# IMU-SD_Card-CAN-CH340.net
KiCad netlist of a schematic drawn in Altium Designer
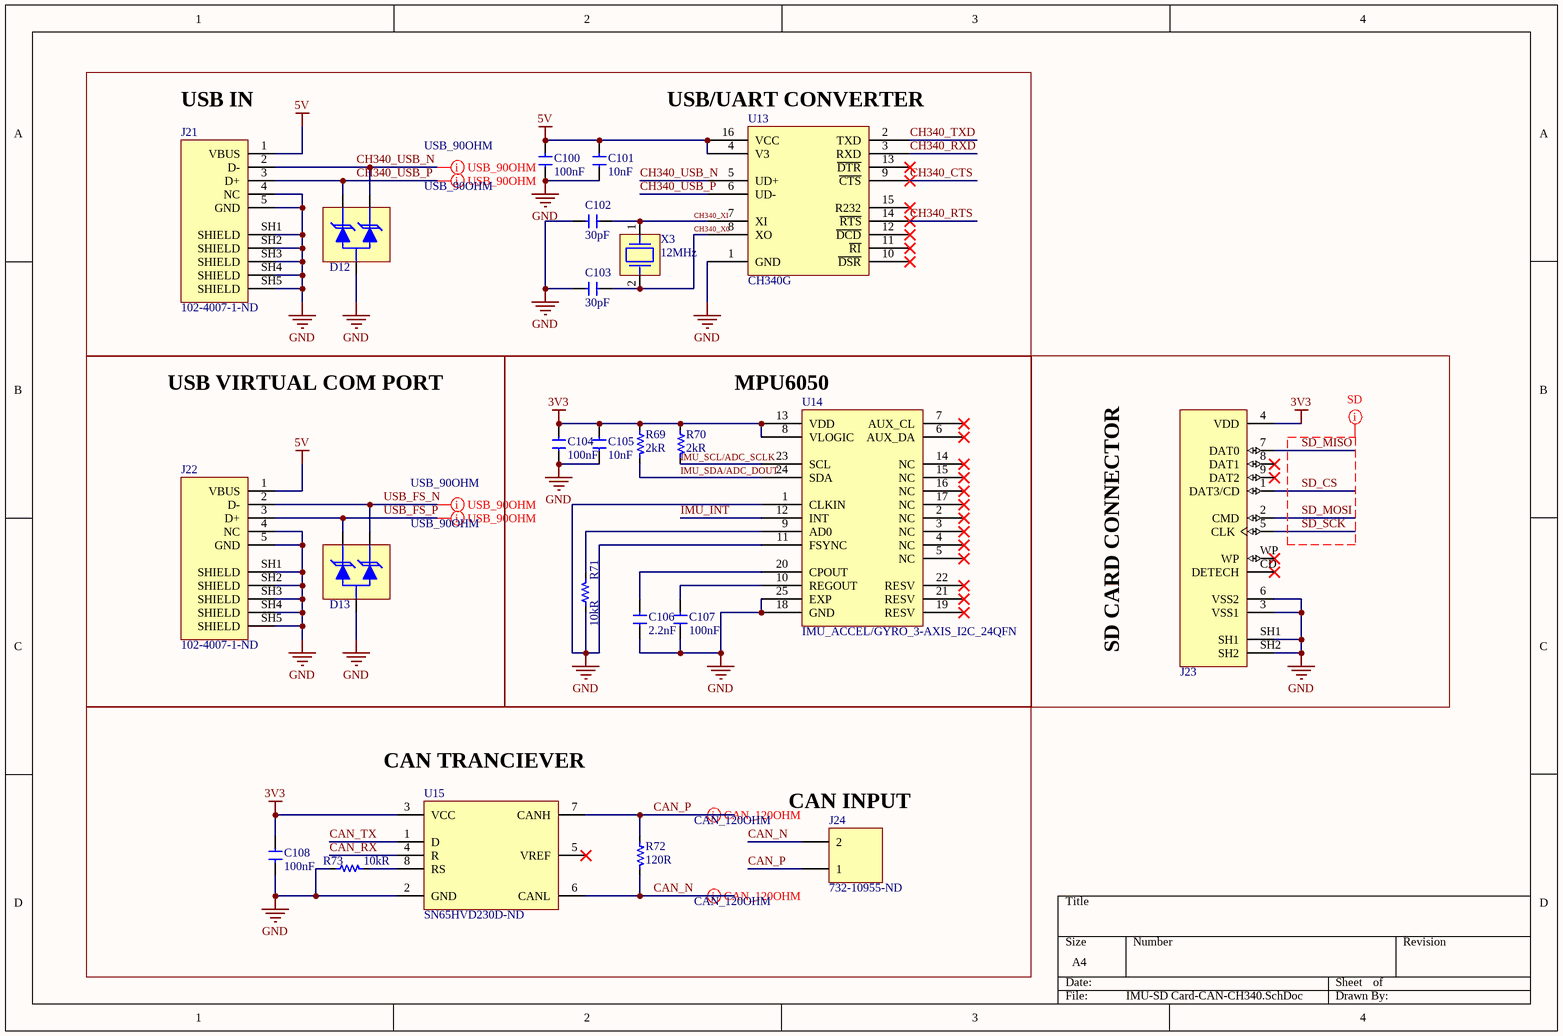
[diagram p0: IMU-SD Card-CAN-CH340.SchDoc]

(export (version "E")
  (design (tool "Eeschema 10.0.6"))
  (components
    (comp (ref "C100")
      (value "CAP_0.1uF_%20_50V_0805_X7R_CER")
      (footprint "0805_CAP")
      (description "Cap Ceramic 0.1uF 50V X7R 20% SMD 0805 125C Paper T/R")
      (fields
        (field (name "MANUFACTURER") "KEMET")
        (field (name "MANUFACTURER PART NUMBER") "C0805C104M5RACTU")
        (field (name "CAPACITANCE") "100nF")
      )
      (libsource (lib "Main Component Library") (part "CAP_0.1uF_%20_50V_0805_X7R_CER"))
    )
    (comp (ref "C101")
      (value "CAP_10nF_%10_50V_0805_X7R_CER")
      (footprint "0805_CAP")
      (description "CAP CER 10000PF 50V X7R 0805")
      (fields
        (field (name "MANUFACTURER") "Samsung")
        (field (name "MANUFACTURER PART NUMBER") "CL21B103KBANNNC")
        (field (name "CAPACITANCE") "10nF")
      )
      (libsource (lib "Main Component Library") (part "CAP_10nF_%10_50V_0805_X7R_CER"))
    )
    (comp (ref "C102")
      (value "CAP_30pF_%5_50V_0805_C0G/NP0_CER")
      (footprint "0805_CAP")
      (description "0805 30 pF 50 V ±5% Tolerance C0G/NP0 Surface Mount Multilayer Ceramic Capacitor")
      (fields
        (field (name "MANUFACTURER") "Kyocera AVX")
        (field (name "MANUFACTURER PART NUMBER") "08055A300JAT2A")
        (field (name "CAPACITANCE") "30pF")
      )
      (libsource (lib "Main Component Library") (part "CAP_30pF_%5_50V_0805_C0G/NP0_CER"))
    )
    (comp (ref "C103")
      (value "CAP_30pF_%5_50V_0805_C0G/NP0_CER")
      (footprint "0805_CAP")
      (description "0805 30 pF 50 V ±5% Tolerance C0G/NP0 Surface Mount Multilayer Ceramic Capacitor")
      (fields
        (field (name "MANUFACTURER") "Kyocera AVX")
        (field (name "MANUFACTURER PART NUMBER") "08055A300JAT2A")
        (field (name "CAPACITANCE") "30pF")
      )
      (libsource (lib "Main Component Library") (part "CAP_30pF_%5_50V_0805_C0G/NP0_CER"))
    )
    (comp (ref "C104")
      (value "CAP_0.1uF_%20_50V_0805_X7R_CER")
      (footprint "0805_CAP")
      (description "Cap Ceramic 0.1uF 50V X7R 20% SMD 0805 125C Paper T/R")
      (fields
        (field (name "MANUFACTURER") "KEMET")
        (field (name "MANUFACTURER PART NUMBER") "C0805C104M5RACTU")
        (field (name "CAPACITANCE") "100nF")
      )
      (libsource (lib "Main Schematic Library") (part "CAP_0.1uF_%20_50V_0805_X7R_CER"))
    )
    (comp (ref "C105")
      (value "CAP_10nF_%10_50V_0805_X7R_CER")
      (footprint "0805_CAP")
      (description "CAP CER 10000PF 50V X7R 0805")
      (fields
        (field (name "MANUFACTURER") "Samsung")
        (field (name "MANUFACTURER PART NUMBER") "CL21B103KBANNNC")
        (field (name "CAPACITANCE") "10nF")
      )
      (libsource (lib "Main Schematic Library") (part "CAP_10nF_%10_50V_0805_X7R_CER"))
    )
    (comp (ref "C106")
      (value "CAP_2200pF_%10_50V_0805_X7R_CER")
      (footprint "0805_CAP")
      (description "贴片陶瓷电容  2.2nF ±10% 50V X7R 0805")
      (fields
        (field (name "MANUFACTURER") "Samsung")
        (field (name "MANUFACTURER PART NUMBER") "CL21B222KBANNNC")
        (field (name "CAPACITANCE") "2.2nF")
      )
      (libsource (lib "Main Schematic Library") (part "CAP_2200pF_%10_50V_0805_X7R_CER"))
    )
    (comp (ref "C107")
      (value "CAP_0.1uF_%20_50V_0805_X7R_CER")
      (footprint "0805_CAP")
      (description "Cap Ceramic 0.1uF 50V X7R 20% SMD 0805 125C Paper T/R")
      (fields
        (field (name "MANUFACTURER") "KEMET")
        (field (name "MANUFACTURER PART NUMBER") "C0805C104M5RACTU")
        (field (name "CAPACITANCE") "100nF")
      )
      (libsource (lib "Main Schematic Library") (part "CAP_0.1uF_%20_50V_0805_X7R_CER"))
    )
    (comp (ref "C108")
      (value "CAP_0.1uF_%20_50V_0805_X7R_CER")
      (footprint "0805_CAP")
      (description "Cap Ceramic 0.1uF 50V X7R 20% SMD 0805 125C Paper T/R")
      (fields
        (field (name "MANUFACTURER") "KEMET")
        (field (name "MANUFACTURER PART NUMBER") "C0805C104M5RACTU")
        (field (name "CAPACITANCE") "100nF")
      )
      (libsource (lib "Main Schematic Library") (part "CAP_0.1uF_%20_50V_0805_X7R_CER"))
    )
    (comp (ref "D12")
      (value "DIODE_TVS_3.3VWM_8VC_SOT23")
      (footprint "SOT170P237X110-3N")
      (description "ESD Suppressor TVS Uni-Dir 3.3V 3-Pin SOT-23 T/R")
      (fields (field (name "MANUFACTURER") "MCC") (field (name "MANUFACTURER PART NUMBER") "ESD3V3AP-TP"))
      (libsource (lib "Main Schematic Library") (part "DIODE_TVS_3.3VWM_8VC_SOT23"))
    )
    (comp (ref "D13")
      (value "DIODE_TVS_3.3VWM_8VC_SOT23")
      (footprint "SOT170P237X110-3N")
      (description "ESD Suppressor TVS Uni-Dir 3.3V 3-Pin SOT-23 T/R")
      (fields (field (name "MANUFACTURER") "MCC") (field (name "MANUFACTURER PART NUMBER") "ESD3V3AP-TP"))
      (libsource (lib "Main Schematic Library") (part "DIODE_TVS_3.3VWM_8VC_SOT23"))
    )
    (comp (ref "J21")
      (value "Micro USB2.0")
      (footprint "MICRO_USB2.0_CUI_UJ2-MIBH2-4-SMT")
      (description "Conn Micro USB 2.0 Type B F 5 POS 0.65mm Solder RA SMD 5 Terminal 1 Port T/R")
      (fields
        (field (name "MANUFACTURER") "CUI Devices")
        (field (name "MANUFACTURER PART NUMBER") "UJ2-MIBH2-4-SMT-TR")
        (field (name "SUPPLIER PART NUMBER 1") "102-4007-1-ND")
      )
      (libsource (lib "Main Schematic Library") (part "CONN_RCPT_USB2.0_MICRO B_SMD_R/A"))
    )
    (comp (ref "J22")
      (value "Micro USB2.0")
      (footprint "MICRO_USB2.0_CUI_UJ2-MIBH2-4-SMT")
      (description "Conn Micro USB 2.0 Type B F 5 POS 0.65mm Solder RA SMD 5 Terminal 1 Port T/R")
      (fields
        (field (name "MANUFACTURER") "CUI Devices")
        (field (name "MANUFACTURER PART NUMBER") "UJ2-MIBH2-4-SMT-TR")
        (field (name "SUPPLIER PART NUMBER 1") "102-4007-1-ND")
      )
      (libsource (lib "Main Schematic Library") (part "CONN_RCPT_USB2.0_MICRO B_SMD_R/A"))
    )
    (comp (ref "J23")
      (value "CONN_SD CARD_L-KLS1-SD-001")
      (footprint "SD CARD L-KLS1-TF-003")
      (description "Conn; IC Socket; SD Memory Card; Push/Push; SD Ser.")
      (fields
        (field (name "MF") "{'manufacturer': u'Amphenol ICC (Commercial Products)'}")
        (field (name "MP") "101003136802")
      )
      (libsource (lib "Main Schematic Library") (part "CONN_SD CARD_L-KLS1-SD-001"))
    )
    (comp (ref "J24")
      (value "CONN_1X2_Terminal Block")
      (footprint "1x2_TERMINAL BLOCK")
      (description "Series 1377 - 5.00 mm Horizontal Entry with Pressure Clamp WR-TBL, 2 pin")
      (fields
        (field (name "MANUFACTURER") "Wurth Electronics")
        (field (name "MANUFACTURER PART NUMBER") "691137710002")
        (field (name "SUPPLIER PART NUMBER 1") "732-10955-ND")
      )
      (libsource (lib "Main Schematic Library") (part "CONN_1X2_Terminal Block"))
    )
    (comp (ref "R69")
      (value "RES_2K OHM_1%_0805_1/8W_SMD")
      (footprint "0805_RES")
      (description "Res Thick Film 0805 2K Ohm 1% 0.125W(1/8W) ±100ppm/C Pad SMD Automotive T/R")
      (fields
        (field (name "MANUFACTURER") "Yageo")
        (field (name "MANUFACTURER PART NUMBER") "AC0805FR-072KL")
        (field (name "RESISTANCE") "2kR")
      )
      (libsource (lib "Main Component Library") (part "RES_2K OHM_1%_0805_1/8W_SMD"))
    )
    (comp (ref "R70")
      (value "RES_2K OHM_1%_0805_1/8W_SMD")
      (footprint "0805_RES")
      (description "Res Thick Film 0805 2K Ohm 1% 0.125W(1/8W) ±100ppm/C Pad SMD Automotive T/R")
      (fields
        (field (name "MANUFACTURER") "Yageo")
        (field (name "MANUFACTURER PART NUMBER") "AC0805FR-072KL")
        (field (name "RESISTANCE") "2kR")
      )
      (libsource (lib "Main Component Library") (part "RES_2K OHM_1%_0805_1/8W_SMD"))
    )
    (comp (ref "R71")
      (value "10k Ohms")
      (footprint "0805_RES")
      (description "Res SMD 0805 10K 1% 0.125W T.C.100PPM")
      (fields
        (field (name "MANUFACTURER") "TDK")
        (field (name "MANUFACTURER PART NUMBER") "C2012X7R1H104K085AA")
        (field (name "RESISTANCE") "10kR")
      )
      (libsource (lib "Main Schematic Library") (part "RES_10K OHM_%1_0805_1/8W"))
    )
    (comp (ref "R72")
      (value "120R")
      (footprint "0805_RES")
      (description "Res Thick Film 0805 120 Ohm 1% 0.125W(1/8W) ±100ppm/C Pad SMD T/R")
      (fields
        (field (name "MANUFACTURER") "Vishay")
        (field (name "MANUFACTURER PART NUMBER") "CRCW0805120RFKEAC")
      )
      (libsource (lib "Main Schematic Library") (part "RES_120 OHM_1%_0805_1/8W"))
    )
    (comp (ref "R73")
      (value "10k Ohms")
      (footprint "0805_RES")
      (description "Res SMD 0805 10K 1% 0.125W T.C.100PPM")
      (fields
        (field (name "MANUFACTURER") "TDK")
        (field (name "MANUFACTURER PART NUMBER") "C2012X7R1H104K085AA")
        (field (name "RESISTANCE") "10kR")
      )
      (libsource (lib "Main Schematic Library") (part "RES_10K OHM_%1_0805_1/8W"))
    )
    (comp (ref "U13")
      (value "CH340G")
      (footprint "SOIC127P600X180-16N")
      (description "USB to UART Converter IC")
      (fields (field (name "MANUFACTURER") "WCH"))
      (libsource (lib "Main Schematic Library") (part "IC_USB/UART_CH340G"))
    )
    (comp (ref "U14")
      (value "IMU_ACCEL/GYRO_3-AXIS_I2C_24QFN")
      (footprint "IC_MPU6050")
      (description "IMU ACCEL/GYRO 3-AXIS I2C 24QFN")
      (fields
        (field (name "MANUFACTURER") "TDK InvenSense")
        (field (name "MANUFACTURER PART NUMBER") "MPU-6050")
      )
      (libsource (lib "Main Schematic Library") (part "IMU_ACCEL/GYRO_3-AXIS_I2C_24QFN"))
    )
    (comp (ref "U15")
      (value "IC_TRANSCEIVER CAN_SN65HVD230D")
      (footprint "SOIC127P599X175-8N")
      (description "SN65HVD230 3.3 V Can Transceiver")
      (fields
        (field (name "MANUFACTURER") "Texas Instruments")
        (field (name "MANUFACTURER PART NUMBER") "SN65HVD230D")
        (field (name "SUPPLIER PART NUMBER 1") "SN65HVD230D-ND")
      )
      (libsource (lib "Main Schematic Library") (part "IC_TRANSCEIVER CAN_SN65HVD230D"))
    )
    (comp (ref "X3")
      (value "CRYSTAL_12MHz_20PF_SMD")
      (footprint "HC-49/US")
      (description "Crystal 12MHz ±25ppm (Tol) ±35ppm (Stability) 20pF FUND 50Ohm 2-Pin HC-49/US SMD T/R")
      (fields
        (field (name "MANUFACTURER") "Abracon")
        (field (name "MANUFACTURER PART NUMBER") "ABLS-12.000MHZ-20-B-3-H-T")
        (field (name "FREQUENCY") "12MHz")
      )
      (libsource (lib "Main Schematic Library") (part "CRYSTAL_12MHz_20PF_SMD"))
    )
  )
  (nets
    (net (code "1") (name "/CAN_N") (class "Default")
      (node (ref "J24") (pin "2") (pinfunction "2_2") (pintype "passive"))
      (node (ref "R72") (pin "1") (pinfunction "1_1") (pintype "passive"))
      (node (ref "U15") (pin "6") (pinfunction "CANL_6") (pintype "passive"))
    )
    (net (code "2") (name "/CAN_P") (class "Default")
      (node (ref "J24") (pin "1") (pinfunction "1_1") (pintype "passive"))
      (node (ref "R72") (pin "2") (pinfunction "2_2") (pintype "passive"))
      (node (ref "U15") (pin "7") (pinfunction "CANH_7") (pintype "passive"))
    )
    (net (code "3") (name "/CAN_RX") (class "Default")
      (node (ref "U15") (pin "4") (pinfunction "R_4") (pintype "passive"))
    )
    (net (code "4") (name "/CAN_TX") (class "Default")
      (node (ref "U15") (pin "1") (pinfunction "D_1") (pintype "passive"))
    )
    (net (code "5") (name "/CH340_CTS") (class "Default")
      (node (ref "U13") (pin "9") (pinfunction "~{CTS}_9") (pintype "passive+no_connect"))
    )
    (net (code "6") (name "/CH340_RTS") (class "Default")
      (node (ref "U13") (pin "14") (pinfunction "~{RTS}_14") (pintype "passive+no_connect"))
    )
    (net (code "7") (name "/CH340_RXD") (class "Default")
      (node (ref "U13") (pin "3") (pinfunction "RXD_3") (pintype "passive"))
    )
    (net (code "8") (name "/CH340_TXD") (class "Default")
      (node (ref "U13") (pin "2") (pinfunction "TXD_2") (pintype "passive"))
    )
    (net (code "9") (name "/CH340_USB_N") (class "Default")
      (node (ref "D12") (pin "1") (pinfunction "CATHODE_1_1") (pintype "passive"))
      (node (ref "J21") (pin "2") (pinfunction "D-_2") (pintype "passive"))
      (node (ref "U13") (pin "5") (pinfunction "UD+_5") (pintype "passive"))
    )
    (net (code "10") (name "/CH340_USB_P") (class "Default")
      (node (ref "D12") (pin "2") (pinfunction "CATHODE_2_2") (pintype "passive"))
      (node (ref "J21") (pin "3") (pinfunction "D+_3") (pintype "passive"))
      (node (ref "U13") (pin "6") (pinfunction "UD-_6") (pintype "passive"))
    )
    (net (code "11") (name "/CH340_X0") (class "Default")
      (node (ref "C103") (pin "2") (pinfunction "2_2") (pintype "passive"))
      (node (ref "U13") (pin "8") (pinfunction "XO_8") (pintype "passive"))
      (node (ref "X3") (pin "2") (pinfunction "2_2") (pintype "passive"))
    )
    (net (code "12") (name "/CH340_XI") (class "Default")
      (node (ref "C102") (pin "2") (pinfunction "2_2") (pintype "passive"))
      (node (ref "U13") (pin "7") (pinfunction "XI_7") (pintype "passive"))
      (node (ref "X3") (pin "1") (pinfunction "1_1") (pintype "passive"))
    )
    (net (code "13") (name "/IMU_INT") (class "Default")
      (node (ref "U14") (pin "12") (pinfunction "INT_12") (pintype "passive"))
    )
    (net (code "14") (name "/IMU_SCL{slash}ADC_SCLK") (class "Default")
      (node (ref "R70") (pin "1") (pinfunction "1_1") (pintype "passive"))
      (node (ref "U14") (pin "23") (pinfunction "SCL_23") (pintype "passive"))
    )
    (net (code "15") (name "/IMU_SDA{slash}ADC_DOUT") (class "Default")
      (node (ref "R69") (pin "1") (pinfunction "1_1") (pintype "passive"))
      (node (ref "U14") (pin "24") (pinfunction "SDA_24") (pintype "passive"))
    )
    (net (code "16") (name "/SD_CS") (class "Default")
      (node (ref "J23") (pin "1") (pinfunction "DAT3/CD_1") (pintype "bidirectional"))
    )
    (net (code "17") (name "/SD_MISO") (class "Default")
      (node (ref "J23") (pin "7") (pinfunction "DAT0_7") (pintype "bidirectional"))
    )
    (net (code "18") (name "/SD_MOSI") (class "Default")
      (node (ref "J23") (pin "2") (pinfunction "CMD_2") (pintype "bidirectional"))
    )
    (net (code "19") (name "/SD_SCK") (class "Default")
      (node (ref "J23") (pin "5") (pinfunction "CLK_5") (pintype "bidirectional"))
    )
    (net (code "20") (name "/USB_FS_N") (class "Default")
      (node (ref "D13") (pin "1") (pinfunction "CATHODE_1_1") (pintype "passive"))
      (node (ref "J22") (pin "2") (pinfunction "D-_2") (pintype "passive"))
    )
    (net (code "21") (name "/USB_FS_P") (class "Default")
      (node (ref "D13") (pin "2") (pinfunction "CATHODE_2_2") (pintype "passive"))
      (node (ref "J22") (pin "3") (pinfunction "D+_3") (pintype "passive"))
    )
    (net (code "22") (name "3V3") (class "Default")
      (node (ref "C104") (pin "2") (pinfunction "2_2") (pintype "passive"))
      (node (ref "C105") (pin "2") (pinfunction "2_2") (pintype "passive"))
      (node (ref "C108") (pin "2") (pinfunction "2_2") (pintype "passive"))
      (node (ref "J23") (pin "4") (pinfunction "VDD_4") (pintype "power_in"))
      (node (ref "R69") (pin "2") (pinfunction "2_2") (pintype "passive"))
      (node (ref "R70") (pin "2") (pinfunction "2_2") (pintype "passive"))
      (node (ref "U14") (pin "13") (pinfunction "VDD_13") (pintype "passive"))
      (node (ref "U14") (pin "8") (pinfunction "VLOGIC_8") (pintype "passive"))
      (node (ref "U15") (pin "3") (pinfunction "VCC_3") (pintype "passive"))
    )
    (net (code "23") (name "5V") (class "Default")
      (node (ref "C100") (pin "2") (pinfunction "2_2") (pintype "passive"))
      (node (ref "C101") (pin "2") (pinfunction "2_2") (pintype "passive"))
      (node (ref "J21") (pin "1") (pinfunction "VBUS_1") (pintype "passive"))
      (node (ref "J22") (pin "1") (pinfunction "VBUS_1") (pintype "passive"))
      (node (ref "U13") (pin "16") (pinfunction "VCC_16") (pintype "passive"))
      (node (ref "U13") (pin "4") (pinfunction "V3_4") (pintype "passive"))
    )
    (net (code "24") (name "GND") (class "Default")
      (node (ref "C100") (pin "1") (pinfunction "1_1") (pintype "passive"))
      (node (ref "C101") (pin "1") (pinfunction "1_1") (pintype "passive"))
      (node (ref "C102") (pin "1") (pinfunction "1_1") (pintype "passive"))
      (node (ref "C103") (pin "1") (pinfunction "1_1") (pintype "passive"))
      (node (ref "C104") (pin "1") (pinfunction "1_1") (pintype "passive"))
      (node (ref "C105") (pin "1") (pinfunction "1_1") (pintype "passive"))
      (node (ref "C106") (pin "1") (pinfunction "1_1") (pintype "passive"))
      (node (ref "C107") (pin "1") (pinfunction "1_1") (pintype "passive"))
      (node (ref "C108") (pin "1") (pinfunction "1_1") (pintype "passive"))
      (node (ref "D12") (pin "3") (pinfunction "ANODE_3") (pintype "passive"))
      (node (ref "D13") (pin "3") (pinfunction "ANODE_3") (pintype "passive"))
      (node (ref "J21") (pin "4") (pinfunction "NC_4") (pintype "passive"))
      (node (ref "J21") (pin "5") (pinfunction "GND_5") (pintype "passive"))
      (node (ref "J21") (pin "SH1") (pinfunction "SHIELD_SH1") (pintype "passive"))
      (node (ref "J21") (pin "SH2") (pinfunction "SHIELD_SH2") (pintype "passive"))
      (node (ref "J21") (pin "SH3") (pinfunction "SHIELD_SH3") (pintype "passive"))
      (node (ref "J21") (pin "SH4") (pinfunction "SHIELD_SH4") (pintype "passive"))
      (node (ref "J21") (pin "SH5") (pinfunction "SHIELD_SH5") (pintype "passive"))
      (node (ref "J22") (pin "4") (pinfunction "NC_4") (pintype "passive"))
      (node (ref "J22") (pin "5") (pinfunction "GND_5") (pintype "passive"))
      (node (ref "J22") (pin "SH1") (pinfunction "SHIELD_SH1") (pintype "passive"))
      (node (ref "J22") (pin "SH2") (pinfunction "SHIELD_SH2") (pintype "passive"))
      (node (ref "J22") (pin "SH3") (pinfunction "SHIELD_SH3") (pintype "passive"))
      (node (ref "J22") (pin "SH4") (pinfunction "SHIELD_SH4") (pintype "passive"))
      (node (ref "J22") (pin "SH5") (pinfunction "SHIELD_SH5") (pintype "passive"))
      (node (ref "J23") (pin "3") (pinfunction "VSS1_3") (pintype "power_in"))
      (node (ref "J23") (pin "6") (pinfunction "VSS2_6") (pintype "passive"))
      (node (ref "J23") (pin "SH1") (pinfunction "SH1_SH1") (pintype "passive"))
      (node (ref "J23") (pin "SH2") (pinfunction "SH2_SH2") (pintype "passive"))
      (node (ref "R71") (pin "2") (pinfunction "2_2") (pintype "passive"))
      (node (ref "R73") (pin "2") (pinfunction "2_2") (pintype "passive"))
      (node (ref "U13") (pin "1") (pinfunction "GND_1") (pintype "passive"))
      (node (ref "U14") (pin "1") (pinfunction "CLKIN_1") (pintype "passive"))
      (node (ref "U14") (pin "11") (pinfunction "FSYNC_11") (pintype "passive"))
      (node (ref "U14") (pin "18") (pinfunction "GND_18") (pintype "passive"))
      (node (ref "U14") (pin "25") (pinfunction "EXP_25") (pintype "power_in"))
      (node (ref "U15") (pin "2") (pinfunction "GND_2") (pintype "passive"))
    )
    (net (code "25") (name "Net-(U14-AD0)") (class "Default")
      (node (ref "R71") (pin "1") (pinfunction "1_1") (pintype "passive"))
      (node (ref "U14") (pin "9") (pinfunction "AD0_9") (pintype "passive"))
    )
    (net (code "26") (name "Net-(U14-CPOUT)") (class "Default")
      (node (ref "C106") (pin "2") (pinfunction "2_2") (pintype "passive"))
      (node (ref "U14") (pin "20") (pinfunction "CPOUT_20") (pintype "passive"))
    )
    (net (code "27") (name "Net-(U14-REGOUT)") (class "Default")
      (node (ref "C107") (pin "2") (pinfunction "2_2") (pintype "passive"))
      (node (ref "U14") (pin "10") (pinfunction "REGOUT_10") (pintype "passive"))
    )
    (net (code "28") (name "Net-(U15-RS)") (class "Default")
      (node (ref "R73") (pin "1") (pinfunction "1_1") (pintype "passive"))
      (node (ref "U15") (pin "8") (pinfunction "RS_8") (pintype "passive"))
    )
    (net (code "29") (name "unconnected-(J23-DAT1-Pad8)") (class "Default")
      (node (ref "J23") (pin "8") (pinfunction "DAT1_8") (pintype "bidirectional+no_connect"))
    )
    (net (code "30") (name "unconnected-(J23-DAT2-Pad9)") (class "Default")
      (node (ref "J23") (pin "9") (pinfunction "DAT2_9") (pintype "bidirectional+no_connect"))
    )
    (net (code "31") (name "unconnected-(J23-DETECH-PadCD)") (class "Default")
      (node (ref "J23") (pin "CD") (pinfunction "DETECH_CD") (pintype "passive+no_connect"))
    )
    (net (code "32") (name "unconnected-(J23-PadWP)") (class "Default")
      (node (ref "J23") (pin "WP") (pinfunction "WP_WP") (pintype "bidirectional+no_connect"))
    )
    (net (code "33") (name "unconnected-(U13-R232-Pad15)") (class "Default")
      (node (ref "U13") (pin "15") (pinfunction "R232_15") (pintype "passive+no_connect"))
    )
    (net (code "34") (name "unconnected-(U13-~{DCD}-Pad12)") (class "Default")
      (node (ref "U13") (pin "12") (pinfunction "~{DCD}_12") (pintype "passive+no_connect"))
    )
    (net (code "35") (name "unconnected-(U13-~{DSR}-Pad10)") (class "Default")
      (node (ref "U13") (pin "10") (pinfunction "~{DSR}_10") (pintype "passive+no_connect"))
    )
    (net (code "36") (name "unconnected-(U13-~{DTR}-Pad13)") (class "Default")
      (node (ref "U13") (pin "13") (pinfunction "~{DTR}_13") (pintype "passive+no_connect"))
    )
    (net (code "37") (name "unconnected-(U13-~{RI}-Pad11)") (class "Default")
      (node (ref "U13") (pin "11") (pinfunction "~{RI}_11") (pintype "passive+no_connect"))
    )
    (net (code "38") (name "unconnected-(U14-AUX_CL-Pad7)") (class "Default")
      (node (ref "U14") (pin "7") (pinfunction "AUX_CL_7") (pintype "passive+no_connect"))
    )
    (net (code "39") (name "unconnected-(U14-AUX_DA-Pad6)") (class "Default")
      (node (ref "U14") (pin "6") (pinfunction "AUX_DA_6") (pintype "passive+no_connect"))
    )
    (net (code "40") (name "unconnected-(U14-NC-Pad2)") (class "Default")
      (node (ref "U14") (pin "2") (pinfunction "NC_2") (pintype "passive+no_connect"))
    )
    (net (code "41") (name "unconnected-(U14-NC-Pad3)") (class "Default")
      (node (ref "U14") (pin "3") (pinfunction "NC_3") (pintype "passive+no_connect"))
    )
    (net (code "42") (name "unconnected-(U14-NC-Pad4)") (class "Default")
      (node (ref "U14") (pin "4") (pinfunction "NC_4") (pintype "passive+no_connect"))
    )
    (net (code "43") (name "unconnected-(U14-NC-Pad5)") (class "Default")
      (node (ref "U14") (pin "5") (pinfunction "NC_5") (pintype "passive+no_connect"))
    )
    (net (code "44") (name "unconnected-(U14-NC-Pad14)") (class "Default")
      (node (ref "U14") (pin "14") (pinfunction "NC_14") (pintype "passive+no_connect"))
    )
    (net (code "45") (name "unconnected-(U14-NC-Pad15)") (class "Default")
      (node (ref "U14") (pin "15") (pinfunction "NC_15") (pintype "passive+no_connect"))
    )
    (net (code "46") (name "unconnected-(U14-NC-Pad16)") (class "Default")
      (node (ref "U14") (pin "16") (pinfunction "NC_16") (pintype "passive+no_connect"))
    )
    (net (code "47") (name "unconnected-(U14-NC-Pad17)") (class "Default")
      (node (ref "U14") (pin "17") (pinfunction "NC_17") (pintype "passive+no_connect"))
    )
    (net (code "48") (name "unconnected-(U14-RESV-Pad19)") (class "Default")
      (node (ref "U14") (pin "19") (pinfunction "RESV_19") (pintype "passive+no_connect"))
    )
    (net (code "49") (name "unconnected-(U14-RESV-Pad21)") (class "Default")
      (node (ref "U14") (pin "21") (pinfunction "RESV_21") (pintype "passive+no_connect"))
    )
    (net (code "50") (name "unconnected-(U14-RESV-Pad22)") (class "Default")
      (node (ref "U14") (pin "22") (pinfunction "RESV_22") (pintype "passive+no_connect"))
    )
    (net (code "51") (name "unconnected-(U15-VREF-Pad5)") (class "Default")
      (node (ref "U15") (pin "5") (pinfunction "VREF_5") (pintype "passive+no_connect"))
    )
  )
)
